# ac_dc.net
KiCad netlist of a schematic drawn in EAGLE
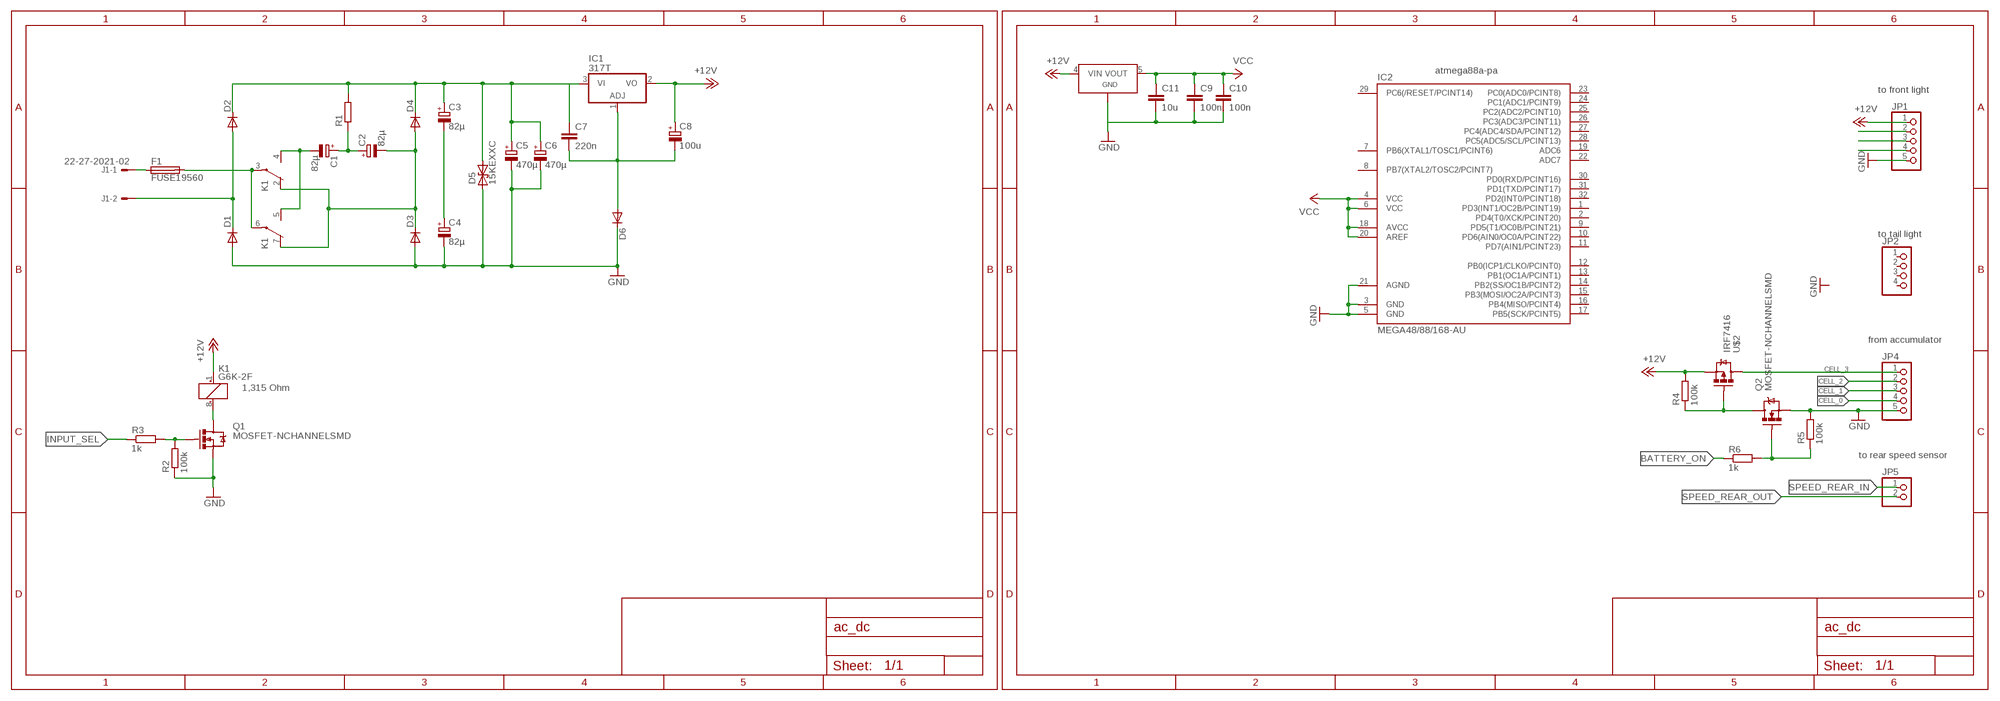
[diagram p0: schematic, sheet 1]

(export (version "E")
  (design (tool "Eeschema 10.0.6"))
  (components
    (comp (ref "C1")
      (value "82µ")
      (footprint "eagle-import:175TMP-0808")
      (libsource (lib "eagle-import") (part "CPOL-EU175TMP-0808"))
    )
    (comp (ref "C2")
      (value "82µ")
      (footprint "eagle-import:175TMP-0808")
      (libsource (lib "eagle-import") (part "CPOL-EU175TMP-0808"))
    )
    (comp (ref "C3")
      (value "82µ")
      (footprint "eagle-import:175TMP-0808")
      (libsource (lib "eagle-import") (part "CPOL-EU175TMP-0808"))
    )
    (comp (ref "C4")
      (value "82µ")
      (footprint "eagle-import:175TMP-0808")
      (libsource (lib "eagle-import") (part "CPOL-EU175TMP-0808"))
    )
    (comp (ref "C5")
      (value "470µ")
      (footprint "eagle-import:153CLV-1014")
      (libsource (lib "eagle-import") (part "CPOL-EU153CLV-1014"))
    )
    (comp (ref "C6")
      (value "470µ")
      (footprint "eagle-import:153CLV-1014")
      (libsource (lib "eagle-import") (part "CPOL-EU153CLV-1014"))
    )
    (comp (ref "C7")
      (value "220n")
      (footprint "eagle-import:C0805")
      (libsource (lib "eagle-import") (part "C-EUC0805"))
    )
    (comp (ref "C8")
      (value "100u")
      (footprint "eagle-import:PANASONIC_E")
      (libsource (lib "eagle-import") (part "CPOL-EUE"))
    )
    (comp (ref "C9")
      (value "100n")
      (footprint "eagle-import:C0805")
      (libsource (lib "eagle-import") (part "C-EUC0805"))
    )
    (comp (ref "C10")
      (value "100n")
      (footprint "eagle-import:C0805")
      (libsource (lib "eagle-import") (part "C-EUC0805"))
    )
    (comp (ref "C11")
      (value "10u")
      (footprint "eagle-import:C1206")
      (libsource (lib "eagle-import") (part "C-EUC1206"))
    )
    (comp (ref "D1")
      (value "DIODE-DO-214AC")
      (footprint "eagle-import:DO-214AC")
      (libsource (lib "eagle-import") (part "DIODE-DO-214AC"))
    )
    (comp (ref "D2")
      (value "DIODE-DO-214AC")
      (footprint "eagle-import:DO-214AC")
      (libsource (lib "eagle-import") (part "DIODE-DO-214AC"))
    )
    (comp (ref "D3")
      (value "DIODE-DO-214AC")
      (footprint "eagle-import:DO-214AC")
      (libsource (lib "eagle-import") (part "DIODE-DO-214AC"))
    )
    (comp (ref "D4")
      (value "DIODE-DO-214AC")
      (footprint "eagle-import:DO-214AC")
      (libsource (lib "eagle-import") (part "DIODE-DO-214AC"))
    )
    (comp (ref "D5")
      (value "15KEXXC")
      (footprint "eagle-import:CB429-17")
      (libsource (lib "eagle-import") (part "15KEXXC"))
    )
    (comp (ref "D6")
      (value "DIODE-MINIMELF")
      (footprint "eagle-import:MINIMELF")
      (libsource (lib "eagle-import") (part "DIODE-MINIMELF"))
    )
    (comp (ref "F1")
      (value "FUSE19560")
      (footprint "eagle-import:19560")
      (fields (field (name "MPN") "56000001009"))
      (libsource (lib "eagle-import") (part "FUSE19560"))
    )
    (comp (ref "IC1")
      (value "317T")
      (footprint "eagle-import:TO220H")
      (libsource (lib "eagle-import") (part "317T"))
    )
    (comp (ref "IC2")
      (value "MEGA48/88/168-AU")
      (footprint "eagle-import:TQFP32-08")
      (libsource (lib "eagle-import") (part "MEGA48/88/168-AU"))
    )
    (comp (ref "J1")
      (value "22-27-2021-02")
      (footprint "eagle-import:6410-02")
      (libsource (lib "eagle-import") (part "22-?-0227-2021"))
    )
    (comp (ref "JP1")
      (value "PINHD-1X5")
      (footprint "eagle-import:1X05")
      (libsource (lib "eagle-import") (part "PINHD-1X5"))
    )
    (comp (ref "JP2")
      (value "PINHD-1X4")
      (footprint "eagle-import:1X04")
      (libsource (lib "eagle-import") (part "PINHD-1X4"))
    )
    (comp (ref "JP4")
      (value "PINHD-1X5")
      (footprint "eagle-import:1X05")
      (libsource (lib "eagle-import") (part "PINHD-1X5"))
    )
    (comp (ref "JP5")
      (value "PINHD-1X2")
      (footprint "eagle-import:1X02")
      (libsource (lib "eagle-import") (part "PINHD-1X2"))
    )
    (comp (ref "K1")
      (value "G6K-2F")
      (footprint "eagle-import:G6K-2F")
      (fields (field (name "MF") "OMRON COMPONENTS USA") (field (name "MPN") "G6K-2F DC24"))
      (libsource (lib "eagle-import") (part "G6K-2F"))
    )
    (comp (ref "Q1")
      (value "MOSFET-NCHANNELSMD")
      (footprint "eagle-import:SOT23-3")
      (libsource (lib "eagle-import") (part "MOSFET-NCHANNELSMD"))
    )
    (comp (ref "Q2")
      (value "MOSFET-NCHANNELSMD")
      (footprint "eagle-import:SOT23-3")
      (libsource (lib "eagle-import") (part "MOSFET-NCHANNELSMD"))
    )
    (comp (ref "R1")
      (value "R-EU_R1206")
      (footprint "eagle-import:R1206")
      (libsource (lib "eagle-import") (part "R-EU_R1206"))
    )
    (comp (ref "R2")
      (value "100k")
      (footprint "eagle-import:R0805")
      (libsource (lib "eagle-import") (part "R-EU_R0805"))
    )
    (comp (ref "R3")
      (value "1k")
      (footprint "eagle-import:R0805")
      (libsource (lib "eagle-import") (part "R-EU_R0805"))
    )
    (comp (ref "R4")
      (value "100k")
      (footprint "eagle-import:R0805")
      (libsource (lib "eagle-import") (part "R-EU_R0805"))
    )
    (comp (ref "R5")
      (value "100k")
      (footprint "eagle-import:R0805")
      (libsource (lib "eagle-import") (part "R-EU_R0805"))
    )
    (comp (ref "R6")
      (value "1k")
      (footprint "eagle-import:R0805")
      (libsource (lib "eagle-import") (part "R-EU_R0805"))
    )
    (comp (ref "U$1")
      (value "TPS71530")
      (footprint "eagle-import:SOT23-DBV")
      (libsource (lib "eagle-import") (part "TPS71530"))
    )
    (comp (ref "U$2")
      (value "IRF7416")
      (footprint "eagle-import:SO8-2")
      (libsource (lib "eagle-import") (part "IRF7416"))
    )
  )
  (nets
    (net (code "1") (name "+12V") (class "Default")
      (node (ref "C8") (pin "+") (pinfunction "+_+") (pintype "passive"))
      (node (ref "IC1") (pin "2") (pinfunction "VO_2") (pintype "passive"))
      (node (ref "JP1") (pin "1") (pinfunction "1_1") (pintype "passive"))
      (node (ref "K1") (pin "1") (pinfunction "+_1") (pintype "passive"))
      (node (ref "R4") (pin "2") (pinfunction "2_2") (pintype "passive"))
      (node (ref "U$1") (pin "4") (pinfunction "VIN_4") (pintype "power_in"))
      (node (ref "U$2") (pin "1") (pinfunction "S1_1") (pintype "passive"))
      (node (ref "U$2") (pin "2") (pinfunction "S1_2") (pintype "passive"))
      (node (ref "U$2") (pin "3") (pinfunction "S1_3") (pintype "passive"))
    )
    (net (code "2") (name "/CELL_3") (class "Default")
      (node (ref "JP4") (pin "1") (pinfunction "1_1") (pintype "passive"))
      (node (ref "U$2") (pin "5") (pinfunction "D1_5") (pintype "passive"))
      (node (ref "U$2") (pin "6") (pinfunction "D1_6") (pintype "passive"))
      (node (ref "U$2") (pin "7") (pinfunction "D1_7") (pintype "passive"))
      (node (ref "U$2") (pin "8") (pinfunction "D1_8") (pintype "passive"))
    )
    (net (code "3") (name "BATTERY_ON") (class "Default")
      (node (ref "R6") (pin "1") (pinfunction "1_1") (pintype "passive"))
    )
    (net (code "4") (name "CELL_0") (class "Default")
      (node (ref "JP4") (pin "4") (pinfunction "4_4") (pintype "passive"))
    )
    (net (code "5") (name "CELL_1") (class "Default")
      (node (ref "JP4") (pin "3") (pinfunction "3_3") (pintype "passive"))
    )
    (net (code "6") (name "CELL_2") (class "Default")
      (node (ref "JP4") (pin "2") (pinfunction "2_2") (pintype "passive"))
    )
    (net (code "7") (name "GND") (class "Default")
      (node (ref "C10") (pin "2") (pinfunction "2_2") (pintype "passive"))
      (node (ref "C11") (pin "2") (pinfunction "2_2") (pintype "passive"))
      (node (ref "C4") (pin "-") (pinfunction "-_-") (pintype "passive"))
      (node (ref "C5") (pin "-") (pinfunction "-_-") (pintype "passive"))
      (node (ref "C6") (pin "-") (pinfunction "-_-") (pintype "passive"))
      (node (ref "C9") (pin "2") (pinfunction "2_2") (pintype "passive"))
      (node (ref "D1") (pin "A") (pinfunction "A_A") (pintype "passive"))
      (node (ref "D3") (pin "A") (pinfunction "A_A") (pintype "passive"))
      (node (ref "D5") (pin "A") (pinfunction "1_A") (pintype "passive"))
      (node (ref "D6") (pin "C") (pinfunction "C_C") (pintype "passive"))
      (node (ref "IC2") (pin "21") (pinfunction "AGND_21") (pintype "power_in"))
      (node (ref "IC2") (pin "3") (pinfunction "GND_3") (pintype "power_in"))
      (node (ref "IC2") (pin "5") (pinfunction "GND_5") (pintype "power_in"))
      (node (ref "JP1") (pin "5") (pinfunction "5_5") (pintype "passive"))
      (node (ref "JP4") (pin "5") (pinfunction "5_5") (pintype "passive"))
      (node (ref "Q1") (pin "2") (pinfunction "S_2") (pintype "passive"))
      (node (ref "Q2") (pin "2") (pinfunction "S_2") (pintype "passive"))
      (node (ref "R2") (pin "1") (pinfunction "1_1") (pintype "passive"))
      (node (ref "R5") (pin "2") (pinfunction "2_2") (pintype "passive"))
      (node (ref "U$1") (pin "2") (pinfunction "GND_2") (pintype "power_in"))
    )
    (net (code "8") (name "INPUT_SEL") (class "Default")
      (node (ref "R3") (pin "1") (pinfunction "1_1") (pintype "passive"))
    )
    (net (code "9") (name "Net-(C1-Pad+)") (class "Default")
      (node (ref "C1") (pin "+") (pinfunction "+_+") (pintype "passive"))
      (node (ref "C2") (pin "+") (pinfunction "+_+") (pintype "passive"))
      (node (ref "R1") (pin "1") (pinfunction "1_1") (pintype "passive"))
    )
    (net (code "10") (name "Net-(C3-Pad-)") (class "Default")
      (node (ref "C3") (pin "-") (pinfunction "-_-") (pintype "passive"))
      (node (ref "C4") (pin "+") (pinfunction "+_+") (pintype "passive"))
    )
    (net (code "11") (name "Net-(D5-2)") (class "Default")
      (node (ref "C3") (pin "+") (pinfunction "+_+") (pintype "passive"))
      (node (ref "C5") (pin "+") (pinfunction "+_+") (pintype "passive"))
      (node (ref "C6") (pin "+") (pinfunction "+_+") (pintype "passive"))
      (node (ref "C7") (pin "1") (pinfunction "1_1") (pintype "passive"))
      (node (ref "D2") (pin "C") (pinfunction "C_C") (pintype "passive"))
      (node (ref "D4") (pin "C") (pinfunction "C_C") (pintype "passive"))
      (node (ref "D5") (pin "C") (pinfunction "2_C") (pintype "passive"))
      (node (ref "IC1") (pin "3") (pinfunction "VI_3") (pintype "input"))
      (node (ref "R1") (pin "2") (pinfunction "2_2") (pintype "passive"))
    )
    (net (code "12") (name "Net-(IC1-ADJ)") (class "Default")
      (node (ref "C7") (pin "2") (pinfunction "2_2") (pintype "passive"))
      (node (ref "C8") (pin "-") (pinfunction "-_-") (pintype "passive"))
      (node (ref "D6") (pin "A") (pinfunction "A_A") (pintype "passive"))
      (node (ref "IC1") (pin "1") (pinfunction "ADJ_1") (pintype "input"))
    )
    (net (code "13") (name "Net-(J1A-S)") (class "Default")
      (node (ref "F1") (pin "1") (pinfunction "1_1") (pintype "passive"))
      (node (ref "J1") (pin "1") (pinfunction "S_1") (pintype "passive"))
    )
    (net (code "14") (name "Net-(J1B-S)") (class "Default")
      (node (ref "D1") (pin "C") (pinfunction "C_C") (pintype "passive"))
      (node (ref "D2") (pin "A") (pinfunction "A_A") (pintype "passive"))
      (node (ref "J1") (pin "2") (pinfunction "S_2") (pintype "passive"))
    )
    (net (code "15") (name "Net-(K1A--)") (class "Default")
      (node (ref "K1") (pin "8") (pinfunction "-_8") (pintype "passive"))
      (node (ref "Q1") (pin "3") (pinfunction "D_3") (pintype "passive"))
    )
    (net (code "16") (name "Net-(K1B-O)") (class "Default")
      (node (ref "C2") (pin "-") (pinfunction "-_-") (pintype "passive"))
      (node (ref "D3") (pin "C") (pinfunction "C_C") (pintype "passive"))
      (node (ref "D4") (pin "A") (pinfunction "A_A") (pintype "passive"))
      (node (ref "K1") (pin "2") (pinfunction "O_2") (pintype "passive"))
      (node (ref "K1") (pin "7") (pinfunction "O_7") (pintype "passive"))
    )
    (net (code "17") (name "Net-(K1B-P)") (class "Default")
      (node (ref "F1") (pin "2") (pinfunction "2_2") (pintype "passive"))
      (node (ref "K1") (pin "3") (pinfunction "P_3") (pintype "passive"))
      (node (ref "K1") (pin "6") (pinfunction "P_6") (pintype "passive"))
    )
    (net (code "18") (name "Net-(K1B-S)") (class "Default")
      (node (ref "C1") (pin "-") (pinfunction "-_-") (pintype "passive"))
      (node (ref "K1") (pin "4") (pinfunction "S_4") (pintype "passive"))
      (node (ref "K1") (pin "5") (pinfunction "S_5") (pintype "passive"))
    )
    (net (code "19") (name "Net-(Q1-G)") (class "Default")
      (node (ref "Q1") (pin "1") (pinfunction "G_1") (pintype "passive"))
      (node (ref "R2") (pin "2") (pinfunction "2_2") (pintype "passive"))
      (node (ref "R3") (pin "2") (pinfunction "2_2") (pintype "passive"))
    )
    (net (code "20") (name "Net-(Q2-D)") (class "Default")
      (node (ref "Q2") (pin "3") (pinfunction "D_3") (pintype "passive"))
      (node (ref "R4") (pin "1") (pinfunction "1_1") (pintype "passive"))
      (node (ref "U$2") (pin "4") (pinfunction "G_4") (pintype "passive"))
    )
    (net (code "21") (name "Net-(Q2-G)") (class "Default")
      (node (ref "Q2") (pin "1") (pinfunction "G_1") (pintype "passive"))
      (node (ref "R5") (pin "1") (pinfunction "1_1") (pintype "passive"))
      (node (ref "R6") (pin "2") (pinfunction "2_2") (pintype "passive"))
    )
    (net (code "22") (name "SPEED_REAR_IN") (class "Default")
      (node (ref "JP5") (pin "1") (pinfunction "1_1") (pintype "passive"))
    )
    (net (code "23") (name "SPEED_REAR_OUT") (class "Default")
      (node (ref "JP5") (pin "2") (pinfunction "2_2") (pintype "passive"))
    )
    (net (code "24") (name "VCC") (class "Default")
      (node (ref "C10") (pin "1") (pinfunction "1_1") (pintype "passive"))
      (node (ref "C11") (pin "1") (pinfunction "1_1") (pintype "passive"))
      (node (ref "C9") (pin "1") (pinfunction "1_1") (pintype "passive"))
      (node (ref "IC2") (pin "18") (pinfunction "AVCC_18") (pintype "passive"))
      (node (ref "IC2") (pin "20") (pinfunction "AREF_20") (pintype "passive"))
      (node (ref "IC2") (pin "4") (pinfunction "VCC_4") (pintype "power_in"))
      (node (ref "IC2") (pin "6") (pinfunction "VCC_6") (pintype "power_in"))
      (node (ref "U$1") (pin "5") (pinfunction "VOUT_5") (pintype "power_in"))
    )
    (net (code "25") (name "unconnected-(IC2-ADC6-Pad19)") (class "Default")
      (node (ref "IC2") (pin "19") (pinfunction "ADC6_19") (pintype "passive"))
    )
    (net (code "26") (name "unconnected-(IC2-ADC7-Pad22)") (class "Default")
      (node (ref "IC2") (pin "22") (pinfunction "ADC7_22") (pintype "passive"))
    )
    (net (code "27") (name "unconnected-(IC2-PB0(ICP1{slash}CLKO{slash}PCINT0)-Pad12)") (class "Default")
      (node (ref "IC2") (pin "12") (pinfunction "PB0(ICP1/CLKO/PCINT0)_12") (pintype "bidirectional"))
    )
    (net (code "28") (name "unconnected-(IC2-PB1(OC1A{slash}PCINT1)-Pad13)") (class "Default")
      (node (ref "IC2") (pin "13") (pinfunction "PB1(OC1A/PCINT1)_13") (pintype "bidirectional"))
    )
    (net (code "29") (name "unconnected-(IC2-PB2(SS{slash}OC1B{slash}PCINT2)-Pad14)") (class "Default")
      (node (ref "IC2") (pin "14") (pinfunction "PB2(SS/OC1B/PCINT2)_14") (pintype "bidirectional"))
    )
    (net (code "30") (name "unconnected-(IC2-PB3(MOSI{slash}OC2A{slash}PCINT3)-Pad15)") (class "Default")
      (node (ref "IC2") (pin "15") (pinfunction "PB3(MOSI/OC2A/PCINT3)_15") (pintype "bidirectional"))
    )
    (net (code "31") (name "unconnected-(IC2-PB4(MISO{slash}PCINT4)-Pad16)") (class "Default")
      (node (ref "IC2") (pin "16") (pinfunction "PB4(MISO/PCINT4)_16") (pintype "bidirectional"))
    )
    (net (code "32") (name "unconnected-(IC2-PB5(SCK{slash}PCINT5)-Pad17)") (class "Default")
      (node (ref "IC2") (pin "17") (pinfunction "PB5(SCK/PCINT5)_17") (pintype "bidirectional"))
    )
    (net (code "33") (name "unconnected-(IC2-PB6(XTAL1{slash}TOSC1{slash}PCINT6)-Pad7)") (class "Default")
      (node (ref "IC2") (pin "7") (pinfunction "PB6(XTAL1/TOSC1/PCINT6)_7") (pintype "bidirectional"))
    )
    (net (code "34") (name "unconnected-(IC2-PB7(XTAL2{slash}TOSC2{slash}PCINT7)-Pad8)") (class "Default")
      (node (ref "IC2") (pin "8") (pinfunction "PB7(XTAL2/TOSC2/PCINT7)_8") (pintype "bidirectional"))
    )
    (net (code "35") (name "unconnected-(IC2-PC0(ADC0{slash}PCINT8)-Pad23)") (class "Default")
      (node (ref "IC2") (pin "23") (pinfunction "PC0(ADC0/PCINT8)_23") (pintype "bidirectional"))
    )
    (net (code "36") (name "unconnected-(IC2-PC1(ADC1{slash}PCINT9)-Pad24)") (class "Default")
      (node (ref "IC2") (pin "24") (pinfunction "PC1(ADC1/PCINT9)_24") (pintype "bidirectional"))
    )
    (net (code "37") (name "unconnected-(IC2-PC2(ADC2{slash}PCINT10)-Pad25)") (class "Default")
      (node (ref "IC2") (pin "25") (pinfunction "PC2(ADC2/PCINT10)_25") (pintype "bidirectional"))
    )
    (net (code "38") (name "unconnected-(IC2-PC3(ADC3{slash}PCINT11)-Pad26)") (class "Default")
      (node (ref "IC2") (pin "26") (pinfunction "PC3(ADC3/PCINT11)_26") (pintype "bidirectional"))
    )
    (net (code "39") (name "unconnected-(IC2-PC4(ADC4{slash}SDA{slash}PCINT12)-Pad27)") (class "Default")
      (node (ref "IC2") (pin "27") (pinfunction "PC4(ADC4/SDA/PCINT12)_27") (pintype "bidirectional"))
    )
    (net (code "40") (name "unconnected-(IC2-PC5(ADC5{slash}SCL{slash}PCINT13)-Pad28)") (class "Default")
      (node (ref "IC2") (pin "28") (pinfunction "PC5(ADC5/SCL/PCINT13)_28") (pintype "bidirectional"))
    )
    (net (code "41") (name "unconnected-(IC2-PC6({slash}RESET{slash}PCINT14)-Pad29)") (class "Default")
      (node (ref "IC2") (pin "29") (pinfunction "PC6(/RESET/PCINT14)_29") (pintype "bidirectional"))
    )
    (net (code "42") (name "unconnected-(IC2-PD0(RXD{slash}PCINT16)-Pad30)") (class "Default")
      (node (ref "IC2") (pin "30") (pinfunction "PD0(RXD/PCINT16)_30") (pintype "bidirectional"))
    )
    (net (code "43") (name "unconnected-(IC2-PD1(TXD{slash}PCINT17)-Pad31)") (class "Default")
      (node (ref "IC2") (pin "31") (pinfunction "PD1(TXD/PCINT17)_31") (pintype "bidirectional"))
    )
    (net (code "44") (name "unconnected-(IC2-PD2(INT0{slash}PCINT18)-Pad32)") (class "Default")
      (node (ref "IC2") (pin "32") (pinfunction "PD2(INT0/PCINT18)_32") (pintype "bidirectional"))
    )
    (net (code "45") (name "unconnected-(IC2-PD3(INT1{slash}OC2B{slash}PCINT19)-Pad1)") (class "Default")
      (node (ref "IC2") (pin "1") (pinfunction "PD3(INT1/OC2B/PCINT19)_1") (pintype "bidirectional"))
    )
    (net (code "46") (name "unconnected-(IC2-PD4(T0{slash}XCK{slash}PCINT20)-Pad2)") (class "Default")
      (node (ref "IC2") (pin "2") (pinfunction "PD4(T0/XCK/PCINT20)_2") (pintype "bidirectional"))
    )
    (net (code "47") (name "unconnected-(IC2-PD5(T1{slash}OC0B{slash}PCINT21)-Pad9)") (class "Default")
      (node (ref "IC2") (pin "9") (pinfunction "PD5(T1/OC0B/PCINT21)_9") (pintype "bidirectional"))
    )
    (net (code "48") (name "unconnected-(IC2-PD6(AIN0{slash}OC0A{slash}PCINT22)-Pad10)") (class "Default")
      (node (ref "IC2") (pin "10") (pinfunction "PD6(AIN0/OC0A/PCINT22)_10") (pintype "bidirectional"))
    )
    (net (code "49") (name "unconnected-(IC2-PD7(AIN1{slash}PCINT23)-Pad11)") (class "Default")
      (node (ref "IC2") (pin "11") (pinfunction "PD7(AIN1/PCINT23)_11") (pintype "bidirectional"))
    )
    (net (code "50") (name "unconnected-(JP1-Pad2)") (class "Default")
      (node (ref "JP1") (pin "2") (pinfunction "2_2") (pintype "passive"))
    )
    (net (code "51") (name "unconnected-(JP1-Pad3)") (class "Default")
      (node (ref "JP1") (pin "3") (pinfunction "3_3") (pintype "passive"))
    )
    (net (code "52") (name "unconnected-(JP1-Pad4)") (class "Default")
      (node (ref "JP1") (pin "4") (pinfunction "4_4") (pintype "passive"))
    )
    (net (code "53") (name "unconnected-(JP2-Pad1)") (class "Default")
      (node (ref "JP2") (pin "1") (pinfunction "1_1") (pintype "passive"))
    )
    (net (code "54") (name "unconnected-(JP2-Pad2)") (class "Default")
      (node (ref "JP2") (pin "2") (pinfunction "2_2") (pintype "passive"))
    )
    (net (code "55") (name "unconnected-(JP2-Pad3)") (class "Default")
      (node (ref "JP2") (pin "3") (pinfunction "3_3") (pintype "passive"))
    )
    (net (code "56") (name "unconnected-(JP2-Pad4)") (class "Default")
      (node (ref "JP2") (pin "4") (pinfunction "4_4") (pintype "passive"))
    )
  )
)
